# LEDDimmerLM3406.net
KiCad netlist of a schematic drawn in EAGLE
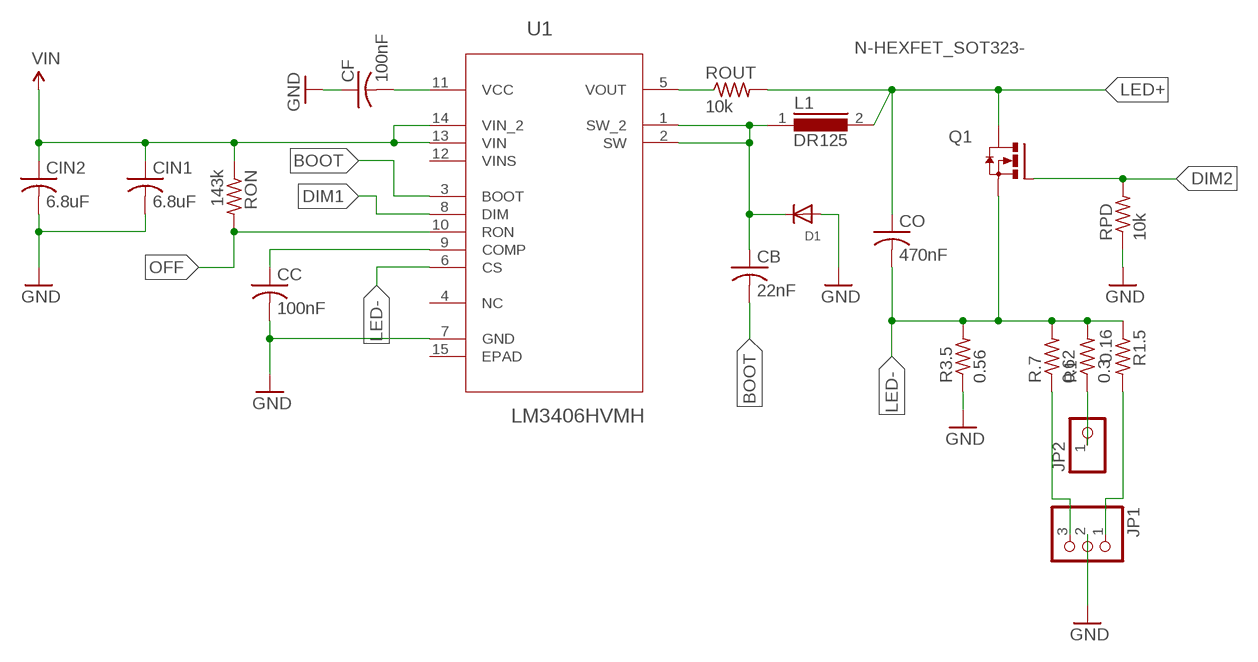
[diagram p0: schematic, sheet 1]

(export (version "E")
  (design (tool "Eeschema 10.0.6"))
  (components
    (comp (ref "CB")
      (value "22nF")
      (footprint "eagle-import:C0603")
      (libsource (lib "eagle-import") (part "C-USC0603"))
    )
    (comp (ref "CC")
      (value "100nF")
      (footprint "eagle-import:C0603")
      (libsource (lib "eagle-import") (part "C-USC0603"))
    )
    (comp (ref "CF")
      (value "100nF")
      (footprint "eagle-import:C0603")
      (libsource (lib "eagle-import") (part "C-USC0603"))
    )
    (comp (ref "CIN1")
      (value "6.8uF")
      (footprint "eagle-import:C1812")
      (libsource (lib "eagle-import") (part "C-USC1812"))
    )
    (comp (ref "CIN2")
      (value "6.8uF")
      (footprint "eagle-import:C1812")
      (libsource (lib "eagle-import") (part "C-USC1812"))
    )
    (comp (ref "CO")
      (value "470nF")
      (footprint "eagle-import:C1206")
      (libsource (lib "eagle-import") (part "C-USC1206"))
    )
    (comp (ref "D1")
      (value "DIODESMA")
      (footprint "eagle-import:SMADIODE")
      (libsource (lib "eagle-import") (part "DIODESMA"))
    )
    (comp (ref "JP1")
      (value "PINHD-1X3")
      (footprint "eagle-import:1X03")
      (libsource (lib "eagle-import") (part "PINHD-1X3"))
    )
    (comp (ref "JP2")
      (value "PINHD-1X1")
      (footprint "eagle-import:1X01")
      (libsource (lib "eagle-import") (part "PINHD-1X1"))
    )
    (comp (ref "L1")
      (value "DR125")
      (footprint "eagle-import:DR125")
      (libsource (lib "eagle-import") (part "DR125"))
    )
    (comp (ref "Q1")
      (value "N-HEXFET_SOT323-")
      (footprint "eagle-import:SOT223")
      (libsource (lib "eagle-import") (part "N-HEXFET_?-SOT323"))
    )
    (comp (ref "R.7")
      (value "0.62")
      (footprint "eagle-import:R0805")
      (libsource (lib "eagle-import") (part "R-US_R0805"))
    )
    (comp (ref "R1")
      (value "0.3")
      (footprint "eagle-import:R0805")
      (libsource (lib "eagle-import") (part "R-US_R0805"))
    )
    (comp (ref "R1.5")
      (value "0.16")
      (footprint "eagle-import:R0805")
      (libsource (lib "eagle-import") (part "R-US_R0805"))
    )
    (comp (ref "R3.5")
      (value "0.56")
      (footprint "eagle-import:R0805")
      (libsource (lib "eagle-import") (part "R-US_R0805"))
    )
    (comp (ref "RON")
      (value "143k")
      (footprint "eagle-import:R0805")
      (libsource (lib "eagle-import") (part "R-US_R0805"))
    )
    (comp (ref "ROUT")
      (value "10k")
      (footprint "eagle-import:R0603")
      (libsource (lib "eagle-import") (part "R-US_R0603"))
    )
    (comp (ref "RPD")
      (value "10k")
      (footprint "eagle-import:R0603")
      (libsource (lib "eagle-import") (part "R-US_R0603"))
    )
    (comp (ref "U1")
      (value "LM3406HVMH")
      (footprint "eagle-import:SOP65P640X110-15N")
      (libsource (lib "eagle-import") (part "LM3406HVMH"))
    )
  )
  (nets
    (net (code "1") (name "BOOT") (class "Default")
      (node (ref "CB") (pin "2") (pinfunction "2_2") (pintype "passive"))
      (node (ref "U1") (pin "3") (pinfunction "BOOT_3") (pintype "input"))
    )
    (net (code "2") (name "DIM1") (class "Default")
      (node (ref "U1") (pin "8") (pinfunction "DIM_8") (pintype "input"))
    )
    (net (code "3") (name "DIM2") (class "Default")
      (node (ref "Q1") (pin "1") (pinfunction "G_1") (pintype "passive"))
      (node (ref "RPD") (pin "2") (pinfunction "2_2") (pintype "passive"))
    )
    (net (code "4") (name "GND") (class "Default")
      (node (ref "CC") (pin "2") (pinfunction "2_2") (pintype "passive"))
      (node (ref "CF") (pin "1") (pinfunction "1_1") (pintype "passive"))
      (node (ref "CIN1") (pin "2") (pinfunction "2_2") (pintype "passive"))
      (node (ref "CIN2") (pin "2") (pinfunction "2_2") (pintype "passive"))
      (node (ref "D1") (pin "A") (pinfunction "A_A") (pintype "passive"))
      (node (ref "JP1") (pin "2") (pinfunction "2_2") (pintype "passive"))
      (node (ref "R3.5") (pin "1") (pinfunction "1_1") (pintype "passive"))
      (node (ref "RPD") (pin "1") (pinfunction "1_1") (pintype "passive"))
      (node (ref "U1") (pin "7") (pinfunction "GND_7") (pintype "passive"))
    )
    (net (code "5") (name "LED+") (class "Default")
      (node (ref "CO") (pin "1") (pinfunction "1_1") (pintype "passive"))
      (node (ref "L1") (pin "2") (pinfunction "2_2") (pintype "passive"))
      (node (ref "Q1") (pin "4") (pinfunction "D_4") (pintype "passive"))
      (node (ref "ROUT") (pin "2") (pinfunction "2_2") (pintype "passive"))
    )
    (net (code "6") (name "LED-") (class "Default")
      (node (ref "CO") (pin "2") (pinfunction "2_2") (pintype "passive"))
      (node (ref "Q1") (pin "3") (pinfunction "S_3") (pintype "passive"))
      (node (ref "R.7") (pin "2") (pinfunction "2_2") (pintype "passive"))
      (node (ref "R1") (pin "2") (pinfunction "2_2") (pintype "passive"))
      (node (ref "R1.5") (pin "1") (pinfunction "1_1") (pintype "passive"))
      (node (ref "R3.5") (pin "2") (pinfunction "2_2") (pintype "passive"))
      (node (ref "U1") (pin "6") (pinfunction "CS_6") (pintype "input"))
    )
    (net (code "7") (name "Net-(JP1-Pad1)") (class "Default")
      (node (ref "JP1") (pin "1") (pinfunction "1_1") (pintype "passive"))
      (node (ref "R1.5") (pin "2") (pinfunction "2_2") (pintype "passive"))
    )
    (net (code "8") (name "Net-(JP1-Pad3)") (class "Default")
      (node (ref "JP1") (pin "3") (pinfunction "3_3") (pintype "passive"))
      (node (ref "R.7") (pin "1") (pinfunction "1_1") (pintype "passive"))
    )
    (net (code "9") (name "Net-(JP2-Pad1)") (class "Default")
      (node (ref "JP2") (pin "1") (pinfunction "1_1") (pintype "passive"))
      (node (ref "R1") (pin "1") (pinfunction "1_1") (pintype "passive"))
    )
    (net (code "10") (name "Net-(U1-COMP)") (class "Default")
      (node (ref "CC") (pin "1") (pinfunction "1_1") (pintype "passive"))
      (node (ref "U1") (pin "9") (pinfunction "COMP_9") (pintype "input"))
    )
    (net (code "11") (name "Net-(U1-SW)") (class "Default")
      (node (ref "CB") (pin "1") (pinfunction "1_1") (pintype "passive"))
      (node (ref "D1") (pin "C") (pinfunction "C_C") (pintype "passive"))
      (node (ref "L1") (pin "1") (pinfunction "1_1") (pintype "passive"))
      (node (ref "U1") (pin "1") (pinfunction "SW_2_1") (pintype "output"))
      (node (ref "U1") (pin "2") (pinfunction "SW_2") (pintype "output"))
    )
    (net (code "12") (name "Net-(U1-VCC)") (class "Default")
      (node (ref "CF") (pin "2") (pinfunction "2_2") (pintype "passive"))
      (node (ref "U1") (pin "11") (pinfunction "VCC_11") (pintype "power_in"))
    )
    (net (code "13") (name "OFF") (class "Default")
      (node (ref "RON") (pin "2") (pinfunction "2_2") (pintype "passive"))
      (node (ref "U1") (pin "10") (pinfunction "RON_10") (pintype "input"))
    )
    (net (code "14") (name "VIN") (class "Default")
      (node (ref "CIN1") (pin "1") (pinfunction "1_1") (pintype "passive"))
      (node (ref "CIN2") (pin "1") (pinfunction "1_1") (pintype "passive"))
      (node (ref "RON") (pin "1") (pinfunction "1_1") (pintype "passive"))
      (node (ref "U1") (pin "13") (pinfunction "VIN_13") (pintype "input"))
      (node (ref "U1") (pin "14") (pinfunction "VIN_2_14") (pintype "input"))
    )
    (net (code "15") (name "unconnected-(ROUT-Pad1)") (class "Default")
      (node (ref "ROUT") (pin "1") (pinfunction "1_1") (pintype "passive"))
    )
    (net (code "16") (name "unconnected-(U1-EPAD-Pad15)") (class "Default")
      (node (ref "U1") (pin "15") (pinfunction "EPAD_15") (pintype "passive"))
    )
    (net (code "17") (name "unconnected-(U1-NC-Pad4)") (class "Default")
      (node (ref "U1") (pin "4") (pinfunction "NC_4") (pintype "no_connect"))
    )
    (net (code "18") (name "unconnected-(U1-VINS-Pad12)") (class "Default")
      (node (ref "U1") (pin "12") (pinfunction "VINS_12") (pintype "input"))
    )
    (net (code "19") (name "unconnected-(U1-VOUT-Pad5)") (class "Default")
      (node (ref "U1") (pin "5") (pinfunction "VOUT_5") (pintype "output"))
    )
  )
)
